# SwitchMult.net
KiCad netlist of a schematic drawn in EAGLE
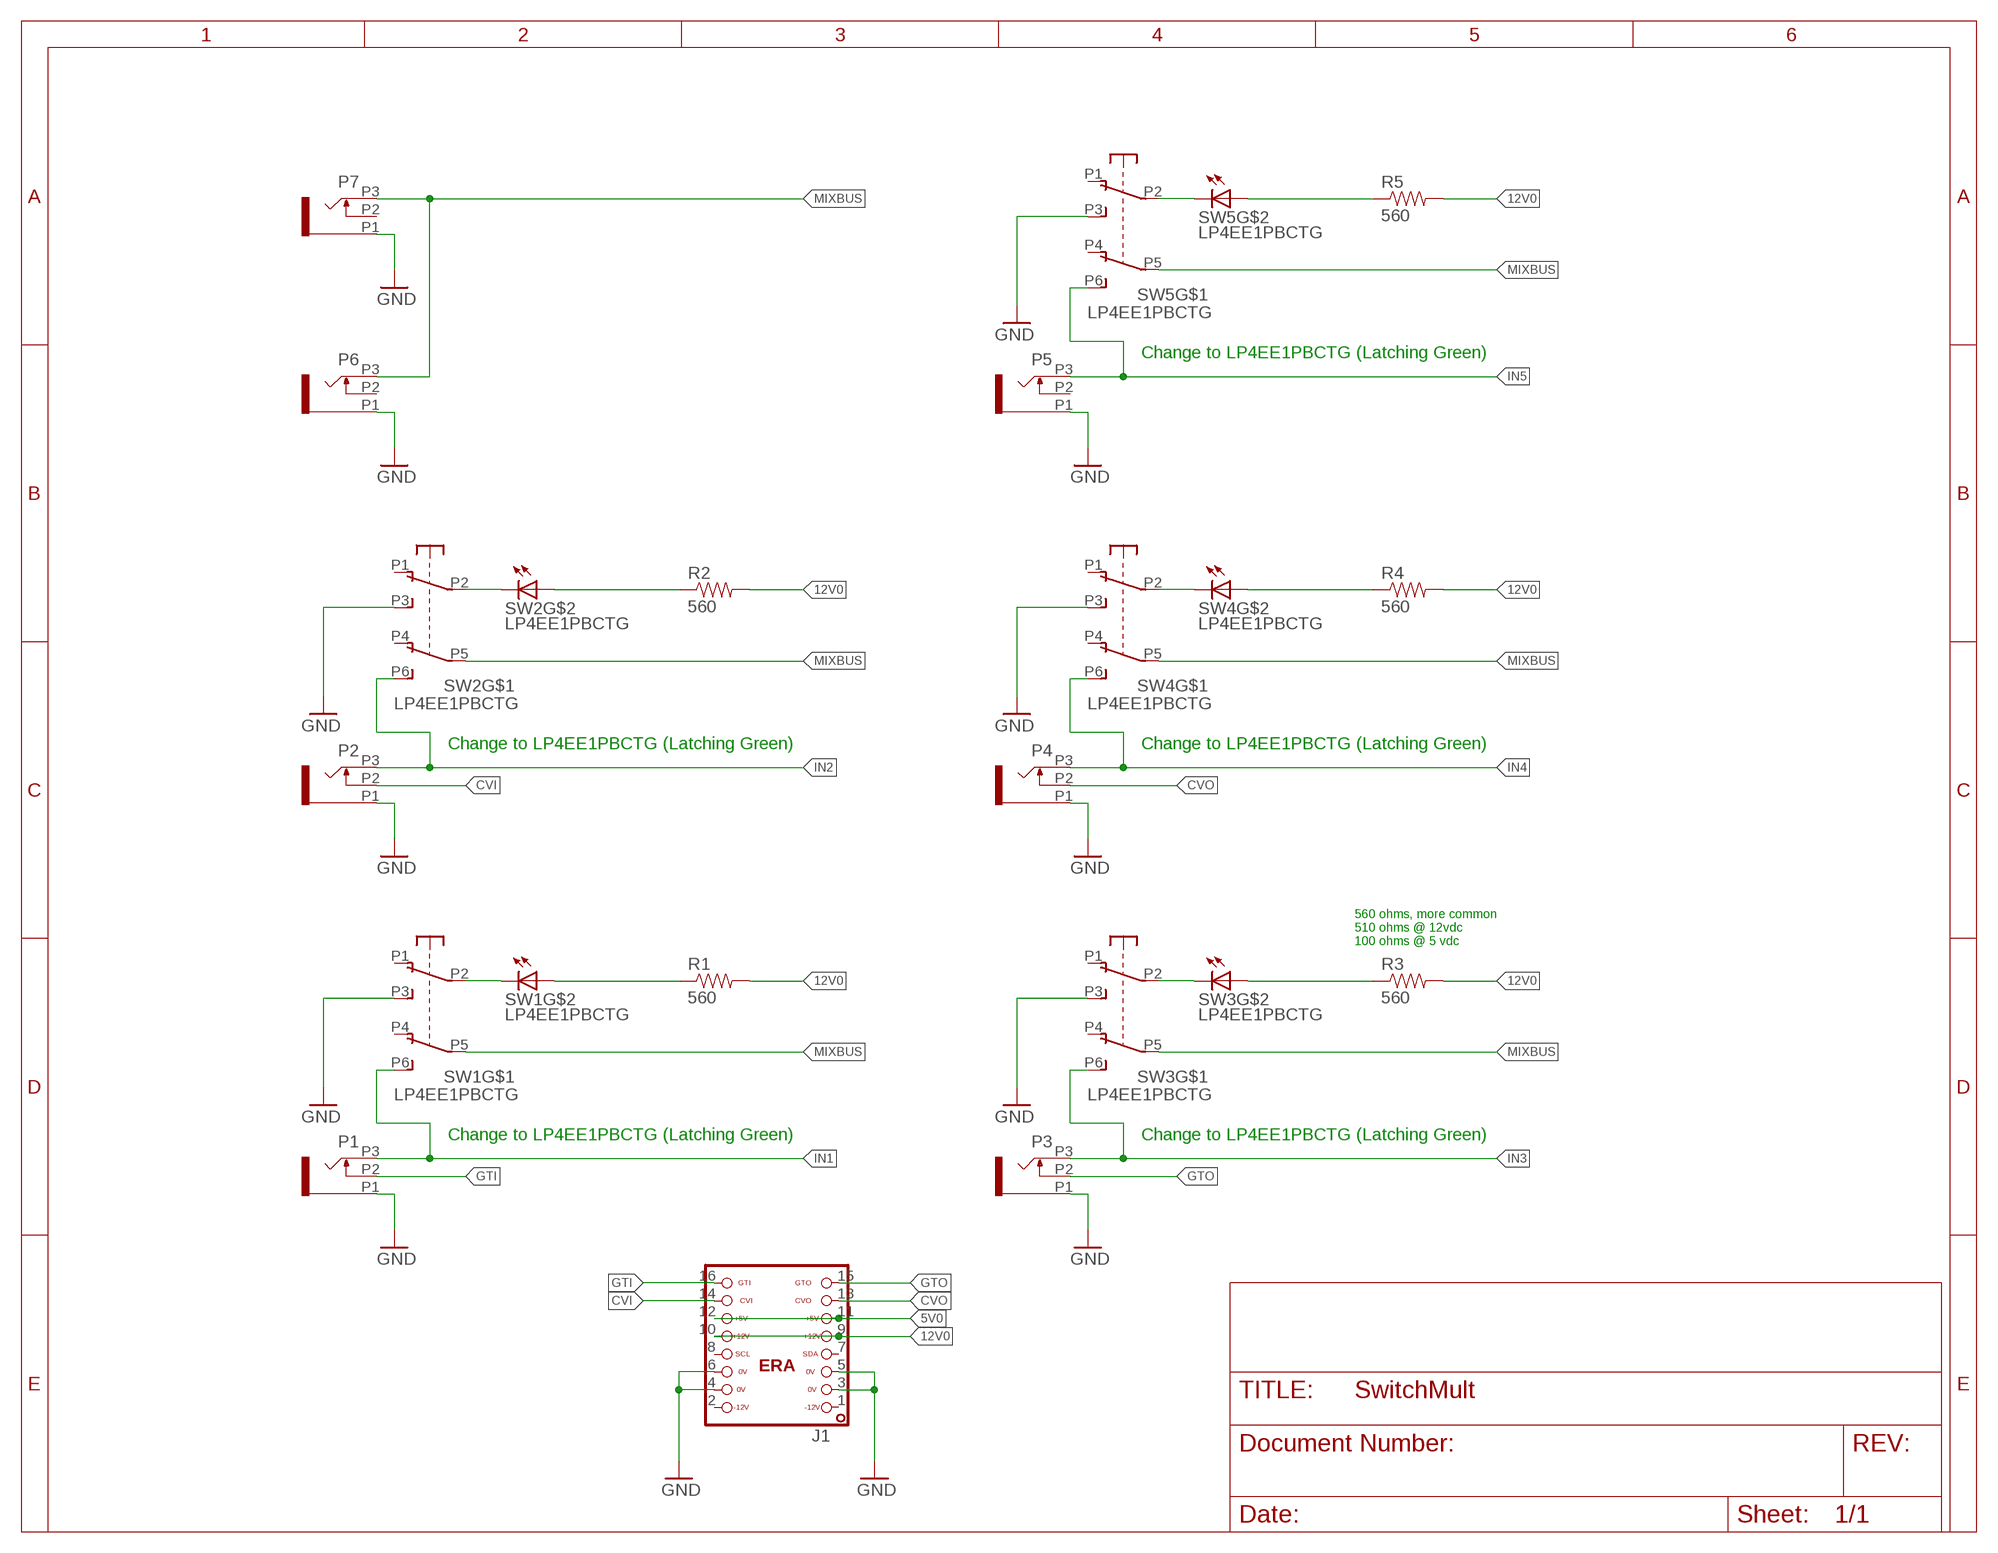
[diagram p0: schematic, sheet 1]

(export (version "E")
  (design (tool "Eeschema 10.0.6"))
  (components
    (comp (ref "J1")
      (value "ERA-SHROUD")
      (footprint "eagle-import:ERA")
      (libsource (lib "eagle-import") (part "ERA-SHROUD"))
    )
    (comp (ref "P1")
      (value "PJ301_THONKICONN6")
      (footprint "eagle-import:WQP_PJ_301M6")
      (libsource (lib "eagle-import") (part "PJ301_THONKICONN6"))
    )
    (comp (ref "P2")
      (value "PJ301_THONKICONN6")
      (footprint "eagle-import:WQP_PJ_301M6")
      (libsource (lib "eagle-import") (part "PJ301_THONKICONN6"))
    )
    (comp (ref "P3")
      (value "PJ301_THONKICONN6")
      (footprint "eagle-import:WQP_PJ_301M6")
      (libsource (lib "eagle-import") (part "PJ301_THONKICONN6"))
    )
    (comp (ref "P4")
      (value "PJ301_THONKICONN6")
      (footprint "eagle-import:WQP_PJ_301M6")
      (libsource (lib "eagle-import") (part "PJ301_THONKICONN6"))
    )
    (comp (ref "P5")
      (value "PJ301_THONKICONN6")
      (footprint "eagle-import:WQP_PJ_301M6")
      (libsource (lib "eagle-import") (part "PJ301_THONKICONN6"))
    )
    (comp (ref "P6")
      (value "PJ301_THONKICONN6")
      (footprint "eagle-import:WQP_PJ_301M6")
      (libsource (lib "eagle-import") (part "PJ301_THONKICONN6"))
    )
    (comp (ref "P7")
      (value "PJ301_THONKICONN6")
      (footprint "eagle-import:WQP_PJ_301M6")
      (libsource (lib "eagle-import") (part "PJ301_THONKICONN6"))
    )
    (comp (ref "R1")
      (value "560")
      (footprint "eagle-import:AXIAL-0.4")
      (libsource (lib "eagle-import") (part "RESISTORPTH-1/4W"))
    )
    (comp (ref "R2")
      (value "560")
      (footprint "eagle-import:AXIAL-0.4")
      (libsource (lib "eagle-import") (part "RESISTORPTH-1/4W"))
    )
    (comp (ref "R3")
      (value "560")
      (footprint "eagle-import:AXIAL-0.4")
      (libsource (lib "eagle-import") (part "RESISTORPTH-1/4W"))
    )
    (comp (ref "R4")
      (value "560")
      (footprint "eagle-import:AXIAL-0.4")
      (libsource (lib "eagle-import") (part "RESISTORPTH-1/4W"))
    )
    (comp (ref "R5")
      (value "560")
      (footprint "eagle-import:AXIAL-0.4")
      (libsource (lib "eagle-import") (part "RESISTORPTH-1/4W"))
    )
    (comp (ref "SW1")
      (value "LP4EE1PBCTG")
      (footprint "eagle-import:LP4OA1PBCT")
      (libsource (lib "eagle-import") (part "LP4OA1PBCT"))
    )
    (comp (ref "SW2")
      (value "LP4EE1PBCTG")
      (footprint "eagle-import:LP4OA1PBCT")
      (libsource (lib "eagle-import") (part "LP4OA1PBCT"))
    )
    (comp (ref "SW3")
      (value "LP4EE1PBCTG")
      (footprint "eagle-import:LP4OA1PBCT")
      (libsource (lib "eagle-import") (part "LP4OA1PBCT"))
    )
    (comp (ref "SW4")
      (value "LP4EE1PBCTG")
      (footprint "eagle-import:LP4OA1PBCT")
      (libsource (lib "eagle-import") (part "LP4OA1PBCT"))
    )
    (comp (ref "SW5")
      (value "LP4EE1PBCTG")
      (footprint "eagle-import:LP4OA1PBCT")
      (libsource (lib "eagle-import") (part "LP4OA1PBCT"))
    )
  )
  (nets
    (net (code "1") (name "5V0") (class "Default")
      (node (ref "J1") (pin "11") (pinfunction "11_11") (pintype "passive"))
      (node (ref "J1") (pin "12") (pinfunction "12_12") (pintype "passive"))
    )
    (net (code "2") (name "12V0") (class "Default")
      (node (ref "J1") (pin "10") (pinfunction "10_10") (pintype "passive"))
      (node (ref "J1") (pin "9") (pinfunction "9_9") (pintype "passive"))
      (node (ref "R1") (pin "P$2") (pinfunction "2_P$2") (pintype "passive"))
      (node (ref "R2") (pin "P$2") (pinfunction "2_P$2") (pintype "passive"))
      (node (ref "R3") (pin "P$2") (pinfunction "2_P$2") (pintype "passive"))
      (node (ref "R4") (pin "P$2") (pinfunction "2_P$2") (pintype "passive"))
      (node (ref "R5") (pin "P$2") (pinfunction "2_P$2") (pintype "passive"))
    )
    (net (code "3") (name "CVI") (class "Default")
      (node (ref "J1") (pin "14") (pinfunction "14_14") (pintype "passive"))
      (node (ref "P2") (pin "P2") (pinfunction "2_P2") (pintype "passive"))
    )
    (net (code "4") (name "CVO") (class "Default")
      (node (ref "J1") (pin "13") (pinfunction "13_13") (pintype "passive"))
      (node (ref "P4") (pin "P2") (pinfunction "2_P2") (pintype "passive"))
    )
    (net (code "5") (name "GND") (class "Default")
      (node (ref "J1") (pin "3") (pinfunction "3_3") (pintype "passive"))
      (node (ref "J1") (pin "4") (pinfunction "4_4") (pintype "passive"))
      (node (ref "J1") (pin "5") (pinfunction "5_5") (pintype "passive"))
      (node (ref "J1") (pin "6") (pinfunction "6_6") (pintype "passive"))
      (node (ref "P1") (pin "P1") (pinfunction "1_P1") (pintype "passive"))
      (node (ref "P2") (pin "P1") (pinfunction "1_P1") (pintype "passive"))
      (node (ref "P3") (pin "P1") (pinfunction "1_P1") (pintype "passive"))
      (node (ref "P4") (pin "P1") (pinfunction "1_P1") (pintype "passive"))
      (node (ref "P5") (pin "P1") (pinfunction "1_P1") (pintype "passive"))
      (node (ref "P6") (pin "P1") (pinfunction "1_P1") (pintype "passive"))
      (node (ref "P7") (pin "P1") (pinfunction "1_P1") (pintype "passive"))
      (node (ref "SW1") (pin "P3") (pinfunction "A3_P3") (pintype "passive"))
      (node (ref "SW2") (pin "P3") (pinfunction "A3_P3") (pintype "passive"))
      (node (ref "SW3") (pin "P3") (pinfunction "A3_P3") (pintype "passive"))
      (node (ref "SW4") (pin "P3") (pinfunction "A3_P3") (pintype "passive"))
      (node (ref "SW5") (pin "P3") (pinfunction "A3_P3") (pintype "passive"))
    )
    (net (code "6") (name "GTI") (class "Default")
      (node (ref "J1") (pin "16") (pinfunction "16_16") (pintype "passive"))
      (node (ref "P1") (pin "P2") (pinfunction "2_P2") (pintype "passive"))
    )
    (net (code "7") (name "GTO") (class "Default")
      (node (ref "J1") (pin "15") (pinfunction "15_15") (pintype "passive"))
      (node (ref "P3") (pin "P2") (pinfunction "2_P2") (pintype "passive"))
    )
    (net (code "8") (name "IN1") (class "Default")
      (node (ref "P1") (pin "P3") (pinfunction "3_P3") (pintype "passive"))
      (node (ref "SW1") (pin "P6") (pinfunction "B3_P6") (pintype "passive"))
    )
    (net (code "9") (name "IN2") (class "Default")
      (node (ref "P2") (pin "P3") (pinfunction "3_P3") (pintype "passive"))
      (node (ref "SW2") (pin "P6") (pinfunction "B3_P6") (pintype "passive"))
    )
    (net (code "10") (name "IN3") (class "Default")
      (node (ref "P3") (pin "P3") (pinfunction "3_P3") (pintype "passive"))
      (node (ref "SW3") (pin "P6") (pinfunction "B3_P6") (pintype "passive"))
    )
    (net (code "11") (name "IN4") (class "Default")
      (node (ref "P4") (pin "P3") (pinfunction "3_P3") (pintype "passive"))
      (node (ref "SW4") (pin "P6") (pinfunction "B3_P6") (pintype "passive"))
    )
    (net (code "12") (name "IN5") (class "Default")
      (node (ref "P5") (pin "P3") (pinfunction "3_P3") (pintype "passive"))
      (node (ref "SW5") (pin "P6") (pinfunction "B3_P6") (pintype "passive"))
    )
    (net (code "13") (name "MIXBUS") (class "Default")
      (node (ref "P6") (pin "P3") (pinfunction "3_P3") (pintype "passive"))
      (node (ref "P7") (pin "P3") (pinfunction "3_P3") (pintype "passive"))
      (node (ref "SW1") (pin "P5") (pinfunction "B2_P5") (pintype "passive"))
      (node (ref "SW2") (pin "P5") (pinfunction "B2_P5") (pintype "passive"))
      (node (ref "SW3") (pin "P5") (pinfunction "B2_P5") (pintype "passive"))
      (node (ref "SW4") (pin "P5") (pinfunction "B2_P5") (pintype "passive"))
      (node (ref "SW5") (pin "P5") (pinfunction "B2_P5") (pintype "passive"))
    )
    (net (code "14") (name "Net-(R1-1)") (class "Default")
      (node (ref "R1") (pin "P$1") (pinfunction "1_P$1") (pintype "passive"))
      (node (ref "SW1") (pin "L1") (pinfunction "L1_L1") (pintype "passive"))
    )
    (net (code "15") (name "Net-(R2-1)") (class "Default")
      (node (ref "R2") (pin "P$1") (pinfunction "1_P$1") (pintype "passive"))
      (node (ref "SW2") (pin "L1") (pinfunction "L1_L1") (pintype "passive"))
    )
    (net (code "16") (name "Net-(R3-1)") (class "Default")
      (node (ref "R3") (pin "P$1") (pinfunction "1_P$1") (pintype "passive"))
      (node (ref "SW3") (pin "L1") (pinfunction "L1_L1") (pintype "passive"))
    )
    (net (code "17") (name "Net-(R4-1)") (class "Default")
      (node (ref "R4") (pin "P$1") (pinfunction "1_P$1") (pintype "passive"))
      (node (ref "SW4") (pin "L1") (pinfunction "L1_L1") (pintype "passive"))
    )
    (net (code "18") (name "Net-(R5-1)") (class "Default")
      (node (ref "R5") (pin "P$1") (pinfunction "1_P$1") (pintype "passive"))
      (node (ref "SW5") (pin "L1") (pinfunction "L1_L1") (pintype "passive"))
    )
    (net (code "19") (name "Net-(SW1A-A2)") (class "Default")
      (node (ref "SW1") (pin "L2") (pinfunction "L2_L2") (pintype "passive"))
      (node (ref "SW1") (pin "P2") (pinfunction "A2_P2") (pintype "passive"))
    )
    (net (code "20") (name "Net-(SW2A-A2)") (class "Default")
      (node (ref "SW2") (pin "L2") (pinfunction "L2_L2") (pintype "passive"))
      (node (ref "SW2") (pin "P2") (pinfunction "A2_P2") (pintype "passive"))
    )
    (net (code "21") (name "Net-(SW3A-A2)") (class "Default")
      (node (ref "SW3") (pin "L2") (pinfunction "L2_L2") (pintype "passive"))
      (node (ref "SW3") (pin "P2") (pinfunction "A2_P2") (pintype "passive"))
    )
    (net (code "22") (name "Net-(SW4A-A2)") (class "Default")
      (node (ref "SW4") (pin "L2") (pinfunction "L2_L2") (pintype "passive"))
      (node (ref "SW4") (pin "P2") (pinfunction "A2_P2") (pintype "passive"))
    )
    (net (code "23") (name "Net-(SW5A-A2)") (class "Default")
      (node (ref "SW5") (pin "L2") (pinfunction "L2_L2") (pintype "passive"))
      (node (ref "SW5") (pin "P2") (pinfunction "A2_P2") (pintype "passive"))
    )
    (net (code "24") (name "unconnected-(J1-Pad1)") (class "Default")
      (node (ref "J1") (pin "1") (pinfunction "1_1") (pintype "passive"))
    )
    (net (code "25") (name "unconnected-(J1-Pad2)") (class "Default")
      (node (ref "J1") (pin "2") (pinfunction "2_2") (pintype "passive"))
    )
    (net (code "26") (name "unconnected-(J1-Pad7)") (class "Default")
      (node (ref "J1") (pin "7") (pinfunction "7_7") (pintype "passive"))
    )
    (net (code "27") (name "unconnected-(J1-Pad8)") (class "Default")
      (node (ref "J1") (pin "8") (pinfunction "8_8") (pintype "passive"))
    )
    (net (code "28") (name "unconnected-(P5-2-PadP2)") (class "Default")
      (node (ref "P5") (pin "P2") (pinfunction "2_P2") (pintype "passive"))
    )
    (net (code "29") (name "unconnected-(P6-2-PadP2)") (class "Default")
      (node (ref "P6") (pin "P2") (pinfunction "2_P2") (pintype "passive"))
    )
    (net (code "30") (name "unconnected-(P7-2-PadP2)") (class "Default")
      (node (ref "P7") (pin "P2") (pinfunction "2_P2") (pintype "passive"))
    )
    (net (code "31") (name "unconnected-(SW1A-A1-PadP1)") (class "Default")
      (node (ref "SW1") (pin "P1") (pinfunction "A1_P1") (pintype "passive"))
    )
    (net (code "32") (name "unconnected-(SW1A-B1-PadP4)") (class "Default")
      (node (ref "SW1") (pin "P4") (pinfunction "B1_P4") (pintype "passive"))
    )
    (net (code "33") (name "unconnected-(SW2A-A1-PadP1)") (class "Default")
      (node (ref "SW2") (pin "P1") (pinfunction "A1_P1") (pintype "passive"))
    )
    (net (code "34") (name "unconnected-(SW2A-B1-PadP4)") (class "Default")
      (node (ref "SW2") (pin "P4") (pinfunction "B1_P4") (pintype "passive"))
    )
    (net (code "35") (name "unconnected-(SW3A-A1-PadP1)") (class "Default")
      (node (ref "SW3") (pin "P1") (pinfunction "A1_P1") (pintype "passive"))
    )
    (net (code "36") (name "unconnected-(SW3A-B1-PadP4)") (class "Default")
      (node (ref "SW3") (pin "P4") (pinfunction "B1_P4") (pintype "passive"))
    )
    (net (code "37") (name "unconnected-(SW4A-A1-PadP1)") (class "Default")
      (node (ref "SW4") (pin "P1") (pinfunction "A1_P1") (pintype "passive"))
    )
    (net (code "38") (name "unconnected-(SW4A-B1-PadP4)") (class "Default")
      (node (ref "SW4") (pin "P4") (pinfunction "B1_P4") (pintype "passive"))
    )
    (net (code "39") (name "unconnected-(SW5A-A1-PadP1)") (class "Default")
      (node (ref "SW5") (pin "P1") (pinfunction "A1_P1") (pintype "passive"))
    )
    (net (code "40") (name "unconnected-(SW5A-B1-PadP4)") (class "Default")
      (node (ref "SW5") (pin "P4") (pinfunction "B1_P4") (pintype "passive"))
    )
  )
)
